# ales_v2_noosc.net
KiCad netlist of a schematic drawn in EAGLE
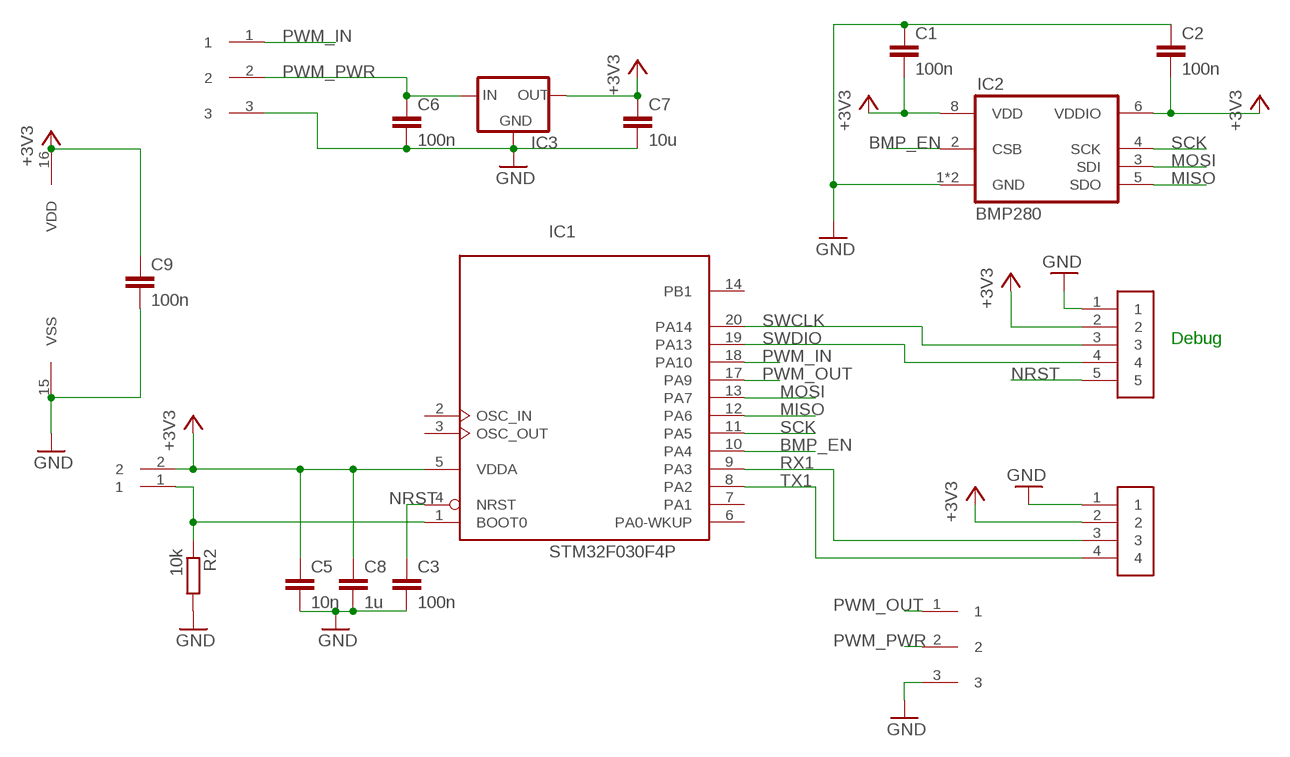
[diagram p0: schematic, sheet 1]

(export (version "E")
  (design (tool "Eeschema 10.0.6"))
  (components
    (comp (ref "BOOT")
      (value "SMD_CONN1X2")
      (footprint "eagle-import:CONN_SMD1X2")
      (libsource (lib "eagle-import") (part "SMD_CONN1X2"))
    )
    (comp (ref "C1")
      (value "100n")
      (footprint "eagle-import:C0603K")
      (libsource (lib "eagle-import") (part "C-EUC0603K"))
    )
    (comp (ref "C2")
      (value "100n")
      (footprint "eagle-import:C0603K")
      (libsource (lib "eagle-import") (part "C-EUC0603K"))
    )
    (comp (ref "C3")
      (value "100n")
      (footprint "eagle-import:C0603K")
      (libsource (lib "eagle-import") (part "C-EUC0603K"))
    )
    (comp (ref "C5")
      (value "10n")
      (footprint "eagle-import:C0603K")
      (libsource (lib "eagle-import") (part "C-EUC0603K"))
    )
    (comp (ref "C6")
      (value "100n")
      (footprint "eagle-import:C0603K")
      (libsource (lib "eagle-import") (part "C-EUC0603K"))
    )
    (comp (ref "C7")
      (value "10u")
      (footprint "eagle-import:C0603K")
      (libsource (lib "eagle-import") (part "C-EUC0603K"))
    )
    (comp (ref "C8")
      (value "1u")
      (footprint "eagle-import:C0603K")
      (libsource (lib "eagle-import") (part "C-EUC0603K"))
    )
    (comp (ref "C9")
      (value "100n")
      (footprint "eagle-import:C0603K")
      (libsource (lib "eagle-import") (part "C-EUC0603K"))
    )
    (comp (ref "IC1")
      (value "STM32F030F4P")
      (footprint "eagle-import:TSSOP20-I")
      (libsource (lib "eagle-import") (part "STM32F030FP4"))
    )
    (comp (ref "IC2")
      (value "BMP280")
      (footprint "eagle-import:BMP280")
      (libsource (lib "eagle-import") (part "BMP280"))
    )
    (comp (ref "IC3")
      (value "XC63FPM")
      (footprint "eagle-import:SOT23")
      (libsource (lib "eagle-import") (part "XC63FPM"))
    )
    (comp (ref "R2")
      (value "10k")
      (footprint "eagle-import:R0603")
      (libsource (lib "eagle-import") (part "R-EU_R0603"))
    )
    (comp (ref "U$2")
      (value "CONN1X3")
      (footprint "eagle-import:CONN1X3")
      (libsource (lib "eagle-import") (part "CONN1X3"))
    )
    (comp (ref "U$3")
      (value "CONN1X3")
      (footprint "eagle-import:CONN1X3")
      (libsource (lib "eagle-import") (part "CONN1X3"))
    )
    (comp (ref "U$4")
      (value "CONN1X4")
      (footprint "eagle-import:CONN1X4")
      (libsource (lib "eagle-import") (part "CONN1X4"))
    )
    (comp (ref "U$6")
      (value "CONN1X5")
      (footprint "eagle-import:CONN1X5")
      (libsource (lib "eagle-import") (part "CONN1X5"))
    )
  )
  (nets
    (net (code "1") (name "+3V3") (class "Default")
      (node (ref "BOOT") (pin "2") (pinfunction "2_2") (pintype "bidirectional"))
      (node (ref "C1") (pin "2") (pinfunction "2_2") (pintype "passive"))
      (node (ref "C2") (pin "2") (pinfunction "2_2") (pintype "passive"))
      (node (ref "C5") (pin "1") (pinfunction "1_1") (pintype "passive"))
      (node (ref "C7") (pin "1") (pinfunction "1_1") (pintype "passive"))
      (node (ref "C8") (pin "1") (pinfunction "1_1") (pintype "passive"))
      (node (ref "C9") (pin "1") (pinfunction "1_1") (pintype "passive"))
      (node (ref "IC1") (pin "16") (pinfunction "VDD_16") (pintype "power_in"))
      (node (ref "IC1") (pin "5") (pinfunction "VDDA_5") (pintype "power_in"))
      (node (ref "IC2") (pin "6") (pinfunction "VDDIO_6") (pintype "power_in"))
      (node (ref "IC2") (pin "8") (pinfunction "VDD_8") (pintype "power_in"))
      (node (ref "IC3") (pin "1") (pinfunction "OUT_1") (pintype "passive"))
      (node (ref "U$4") (pin "2") (pinfunction "2_2") (pintype "bidirectional"))
      (node (ref "U$6") (pin "2") (pinfunction "2_2") (pintype "bidirectional"))
    )
    (net (code "2") (name "/BMP_EN") (class "Default")
      (node (ref "IC1") (pin "10") (pinfunction "PA4_10") (pintype "bidirectional"))
      (node (ref "IC2") (pin "2") (pinfunction "CSB_2") (pintype "input"))
    )
    (net (code "3") (name "/MISO") (class "Default")
      (node (ref "IC1") (pin "12") (pinfunction "PA6_12") (pintype "bidirectional"))
      (node (ref "IC2") (pin "5") (pinfunction "SDO_5") (pintype "input"))
    )
    (net (code "4") (name "/MOSI") (class "Default")
      (node (ref "IC1") (pin "13") (pinfunction "PA7_13") (pintype "bidirectional"))
      (node (ref "IC2") (pin "3") (pinfunction "SDI_3") (pintype "bidirectional"))
    )
    (net (code "5") (name "/NRST") (class "Default")
      (node (ref "C3") (pin "1") (pinfunction "1_1") (pintype "passive"))
      (node (ref "IC1") (pin "4") (pinfunction "NRST_4") (pintype "bidirectional"))
      (node (ref "U$6") (pin "5") (pinfunction "5_5") (pintype "bidirectional"))
    )
    (net (code "6") (name "/PWM_IN") (class "Default")
      (node (ref "IC1") (pin "18") (pinfunction "PA10_18") (pintype "bidirectional"))
      (node (ref "U$3") (pin "1") (pinfunction "1_1") (pintype "bidirectional"))
    )
    (net (code "7") (name "/PWM_OUT") (class "Default")
      (node (ref "IC1") (pin "17") (pinfunction "PA9_17") (pintype "bidirectional"))
      (node (ref "U$2") (pin "1") (pinfunction "1_1") (pintype "bidirectional"))
    )
    (net (code "8") (name "/PWM_PWR") (class "Default")
      (node (ref "C6") (pin "1") (pinfunction "1_1") (pintype "passive"))
      (node (ref "IC3") (pin "2") (pinfunction "IN_2") (pintype "input"))
      (node (ref "U$2") (pin "2") (pinfunction "2_2") (pintype "bidirectional"))
      (node (ref "U$3") (pin "2") (pinfunction "2_2") (pintype "bidirectional"))
    )
    (net (code "9") (name "/RX1") (class "Default")
      (node (ref "IC1") (pin "9") (pinfunction "PA3_9") (pintype "bidirectional"))
      (node (ref "U$4") (pin "3") (pinfunction "3_3") (pintype "bidirectional"))
    )
    (net (code "10") (name "/SCK") (class "Default")
      (node (ref "IC1") (pin "11") (pinfunction "PA5_11") (pintype "bidirectional"))
      (node (ref "IC2") (pin "4") (pinfunction "SCK_4") (pintype "bidirectional"))
    )
    (net (code "11") (name "/SWCLK") (class "Default")
      (node (ref "IC1") (pin "20") (pinfunction "PA14_20") (pintype "bidirectional"))
      (node (ref "U$6") (pin "3") (pinfunction "3_3") (pintype "bidirectional"))
    )
    (net (code "12") (name "/SWDIO") (class "Default")
      (node (ref "IC1") (pin "19") (pinfunction "PA13_19") (pintype "bidirectional"))
      (node (ref "U$6") (pin "4") (pinfunction "4_4") (pintype "bidirectional"))
    )
    (net (code "13") (name "/TX1") (class "Default")
      (node (ref "IC1") (pin "8") (pinfunction "PA2_8") (pintype "bidirectional"))
      (node (ref "U$4") (pin "4") (pinfunction "4_4") (pintype "bidirectional"))
    )
    (net (code "14") (name "GND") (class "Default")
      (node (ref "C1") (pin "1") (pinfunction "1_1") (pintype "passive"))
      (node (ref "C2") (pin "1") (pinfunction "1_1") (pintype "passive"))
      (node (ref "C3") (pin "2") (pinfunction "2_2") (pintype "passive"))
      (node (ref "C5") (pin "2") (pinfunction "2_2") (pintype "passive"))
      (node (ref "C6") (pin "2") (pinfunction "2_2") (pintype "passive"))
      (node (ref "C7") (pin "2") (pinfunction "2_2") (pintype "passive"))
      (node (ref "C8") (pin "2") (pinfunction "2_2") (pintype "passive"))
      (node (ref "C9") (pin "2") (pinfunction "2_2") (pintype "passive"))
      (node (ref "IC1") (pin "15") (pinfunction "VSS_15") (pintype "power_in"))
      (node (ref "IC2") (pin "1") (pinfunction "GND_1") (pintype "power_in"))
      (node (ref "IC2") (pin "7") (pinfunction "GND_7") (pintype "power_in"))
      (node (ref "IC3") (pin "3") (pinfunction "GND_3") (pintype "input"))
      (node (ref "R2") (pin "2") (pinfunction "2_2") (pintype "passive"))
      (node (ref "U$2") (pin "3") (pinfunction "3_3") (pintype "bidirectional"))
      (node (ref "U$3") (pin "3") (pinfunction "3_3") (pintype "bidirectional"))
      (node (ref "U$4") (pin "1") (pinfunction "1_1") (pintype "bidirectional"))
      (node (ref "U$6") (pin "1") (pinfunction "1_1") (pintype "bidirectional"))
    )
    (net (code "15") (name "Net-(IC1A-BOOT0)") (class "Default")
      (node (ref "BOOT") (pin "1") (pinfunction "1_1") (pintype "bidirectional"))
      (node (ref "IC1") (pin "1") (pinfunction "BOOT0_1") (pintype "input"))
      (node (ref "R2") (pin "1") (pinfunction "1_1") (pintype "passive"))
    )
    (net (code "16") (name "unconnected-(IC1A-OSC_IN-Pad2)") (class "Default")
      (node (ref "IC1") (pin "2") (pinfunction "OSC_IN_2") (pintype "bidirectional"))
    )
    (net (code "17") (name "unconnected-(IC1A-OSC_OUT-Pad3)") (class "Default")
      (node (ref "IC1") (pin "3") (pinfunction "OSC_OUT_3") (pintype "bidirectional"))
    )
    (net (code "18") (name "unconnected-(IC1A-PA0-WKUP-Pad6)") (class "Default")
      (node (ref "IC1") (pin "6") (pinfunction "PA0-WKUP_6") (pintype "bidirectional"))
    )
    (net (code "19") (name "unconnected-(IC1A-PA1-Pad7)") (class "Default")
      (node (ref "IC1") (pin "7") (pinfunction "PA1_7") (pintype "bidirectional"))
    )
    (net (code "20") (name "unconnected-(IC1A-PB1-Pad14)") (class "Default")
      (node (ref "IC1") (pin "14") (pinfunction "PB1_14") (pintype "bidirectional"))
    )
  )
)
